# LB_BIT_p1_POWER-v02_rev1.net
KiCad netlist of a schematic drawn in EAGLE
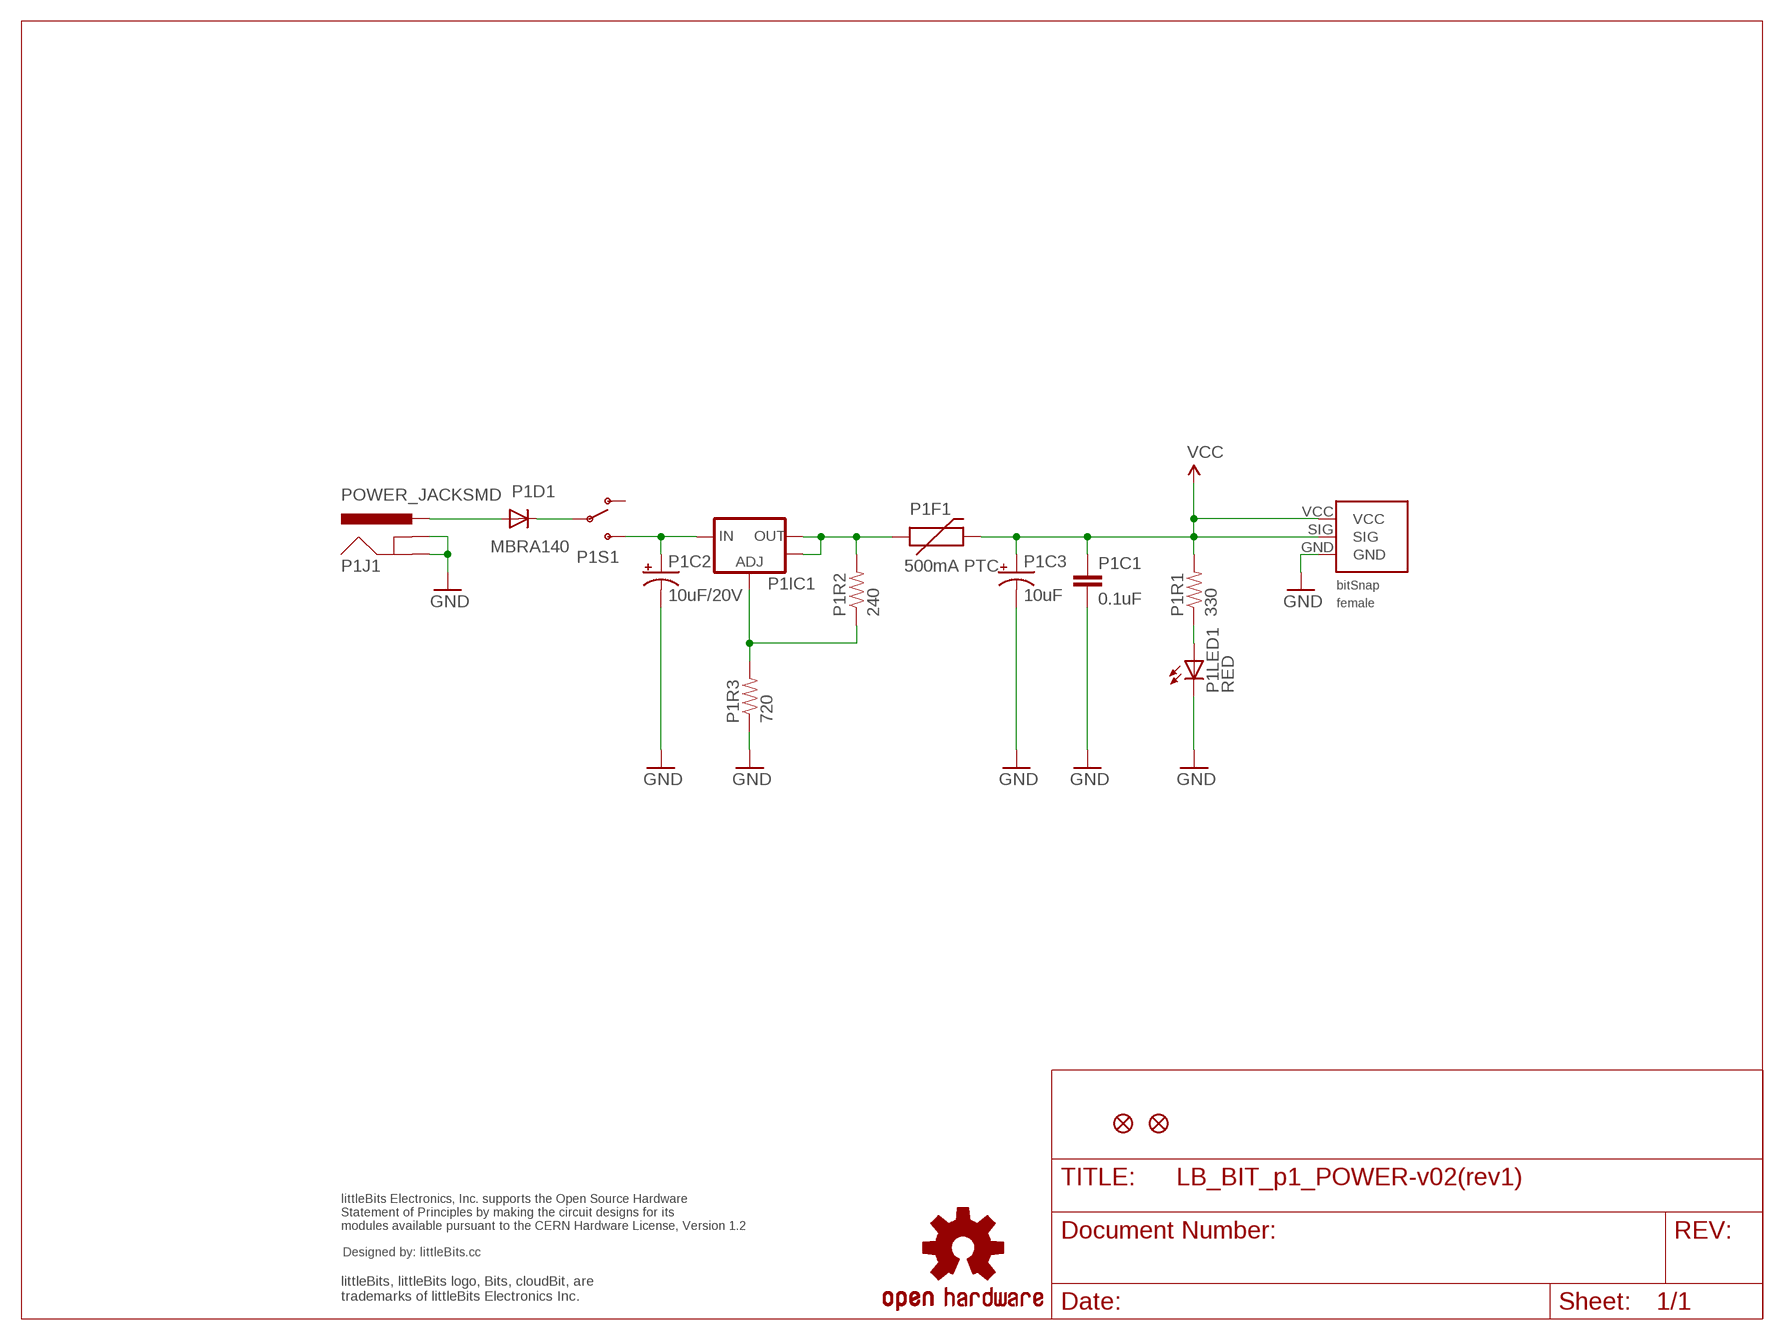
[diagram p0: schematic, sheet 1]

(export (version "E")
  (design (tool "Eeschema 10.0.6"))
  (components
    (comp (ref "JP1")
      (value "FIDUCIAL1X2.5")
      (footprint "eagle-import:FIDUCIAL-1X2.5")
      (libsource (lib "eagle-import") (part "FIDUCIAL1X2.5"))
    )
    (comp (ref "JP2")
      (value "FIDUCIAL1X2.5")
      (footprint "eagle-import:FIDUCIAL-1X2.5")
      (libsource (lib "eagle-import") (part "FIDUCIAL1X2.5"))
    )
    (comp (ref "P1BSF")
      (value "BITSNAP_FEMALE")
      (footprint "eagle-import:BITSNAP_FEMALE")
      (libsource (lib "eagle-import") (part "BITSNAP_FEMALE"))
    )
    (comp (ref "P1C1")
      (value "0.1uF")
      (footprint "eagle-import:0603-CAP")
      (libsource (lib "eagle-import") (part "CAP0603-CAP"))
    )
    (comp (ref "P1C2")
      (value "10uF/20V")
      (footprint "eagle-import:EIA3528")
      (libsource (lib "eagle-import") (part "CAP_POL3528"))
    )
    (comp (ref "P1C3")
      (value "10uF")
      (footprint "eagle-import:EIA3216")
      (libsource (lib "eagle-import") (part "CAP_POL1206"))
    )
    (comp (ref "P1D1")
      (value "MBRA140")
      (footprint "eagle-import:SMA-DIODE")
      (libsource (lib "eagle-import") (part "DIODESMA"))
    )
    (comp (ref "P1F1")
      (value "500mA PTC")
      (footprint "eagle-import:PTC-1206")
      (libsource (lib "eagle-import") (part "PTCSMD"))
    )
    (comp (ref "P1IC1")
      (value "V_REG_LM1117SOT223")
      (footprint "eagle-import:SOT223")
      (libsource (lib "eagle-import") (part "V_REG_LM1117SOT223"))
    )
    (comp (ref "P1J1")
      (value "POWER_JACKSMD")
      (footprint "eagle-import:POWER_JACK_SMD")
      (libsource (lib "eagle-import") (part "POWER_JACKSMD"))
    )
    (comp (ref "P1LED1")
      (value "RED")
      (footprint "eagle-import:LED-1206")
      (libsource (lib "eagle-import") (part "LED1206"))
    )
    (comp (ref "P1R1")
      (value "330")
      (footprint "eagle-import:0603-RES")
      (libsource (lib "eagle-import") (part "RESISTOR0603-RES"))
    )
    (comp (ref "P1R2")
      (value "240")
      (footprint "eagle-import:0603-RES")
      (libsource (lib "eagle-import") (part "RESISTOR0603-RES"))
    )
    (comp (ref "P1R3")
      (value "720")
      (footprint "eagle-import:0603-RES")
      (libsource (lib "eagle-import") (part "RESISTOR0603-RES"))
    )
    (comp (ref "P1S1")
      (value "SWITCH-SPSTSMD")
      (footprint "eagle-import:AYZ0202")
      (libsource (lib "eagle-import") (part "SWITCH-SPSTSMD"))
    )
    (comp (ref "U$1")
      (value "OSHWCREDIT")
      (footprint "eagle-import:OSHWCREDIT")
      (libsource (lib "eagle-import") (part "OSHWCREDIT"))
    )
    (comp (ref "U$3")
      (value "OSHW-LOGOL")
      (footprint "eagle-import:OSHW-LOGO-L")
      (libsource (lib "eagle-import") (part "OSHW-LOGOL"))
    )
  )
  (nets
    (net (code "1") (name "GND") (class "Default")
      (node (ref "P1BSF") (pin "GND") (pinfunction "GND_GND") (pintype "bidirectional"))
      (node (ref "P1C1") (pin "2") (pinfunction "2_2") (pintype "passive"))
      (node (ref "P1C2") (pin "C") (pinfunction "-_C") (pintype "passive"))
      (node (ref "P1C3") (pin "C") (pinfunction "-_C") (pintype "passive"))
      (node (ref "P1J1") (pin "GND") (pinfunction "GNDBREAK_GND") (pintype "bidirectional"))
      (node (ref "P1J1") (pin "P$4") (pinfunction "GND_P$4") (pintype "bidirectional"))
      (node (ref "P1LED1") (pin "C") (pinfunction "C_C") (pintype "passive"))
      (node (ref "P1R3") (pin "1") (pinfunction "1_1") (pintype "passive"))
    )
    (net (code "2") (name "Net-(P1C2-+)") (class "Default")
      (node (ref "P1C2") (pin "A") (pinfunction "+_A") (pintype "passive"))
      (node (ref "P1IC1") (pin "3") (pinfunction "IN_3") (pintype "input"))
      (node (ref "P1S1") (pin "3") (pinfunction "S_3") (pintype "passive"))
    )
    (net (code "3") (name "Net-(P1F1-Pad1)") (class "Default")
      (node (ref "P1F1") (pin "1") (pinfunction "1_1") (pintype "bidirectional"))
      (node (ref "P1IC1") (pin "2") (pinfunction "OUT_2") (pintype "output"))
      (node (ref "P1IC1") (pin "4") (pinfunction "OUT_4") (pintype "output"))
      (node (ref "P1R2") (pin "2") (pinfunction "2_2") (pintype "passive"))
    )
    (net (code "4") (name "Net-(P1IC1-ADJ)") (class "Default")
      (node (ref "P1IC1") (pin "1") (pinfunction "ADJ_1") (pintype "input"))
      (node (ref "P1R2") (pin "1") (pinfunction "1_1") (pintype "passive"))
      (node (ref "P1R3") (pin "2") (pinfunction "2_2") (pintype "passive"))
    )
    (net (code "5") (name "Net-(P1J1-PWR)") (class "Default")
      (node (ref "P1D1") (pin "A") (pinfunction "A_A") (pintype "passive"))
      (node (ref "P1J1") (pin "VIN0") (pinfunction "PWR_VIN0") (pintype "bidirectional"))
    )
    (net (code "6") (name "Net-(P1LED1-PadA)") (class "Default")
      (node (ref "P1LED1") (pin "A") (pinfunction "A_A") (pintype "passive"))
      (node (ref "P1R1") (pin "1") (pinfunction "1_1") (pintype "passive"))
    )
    (net (code "7") (name "Net-(P1S1-P)") (class "Default")
      (node (ref "P1D1") (pin "C") (pinfunction "C_C") (pintype "passive"))
      (node (ref "P1S1") (pin "2") (pinfunction "P_2") (pintype "passive"))
    )
    (net (code "8") (name "VCC") (class "Default")
      (node (ref "P1BSF") (pin "SIG") (pinfunction "SIG_SIG") (pintype "bidirectional"))
      (node (ref "P1BSF") (pin "VCC") (pinfunction "VCC_VCC") (pintype "bidirectional"))
      (node (ref "P1C1") (pin "1") (pinfunction "1_1") (pintype "passive"))
      (node (ref "P1C3") (pin "A") (pinfunction "+_A") (pintype "passive"))
      (node (ref "P1F1") (pin "2") (pinfunction "2_2") (pintype "bidirectional"))
      (node (ref "P1R1") (pin "2") (pinfunction "2_2") (pintype "passive"))
    )
    (net (code "9") (name "unconnected-(P1S1-O-Pad1)") (class "Default")
      (node (ref "P1S1") (pin "1") (pinfunction "O_1") (pintype "passive"))
    )
  )
)
